# IOTA-GFT-Shield-a.net
KiCad netlist of a schematic drawn in EAGLE
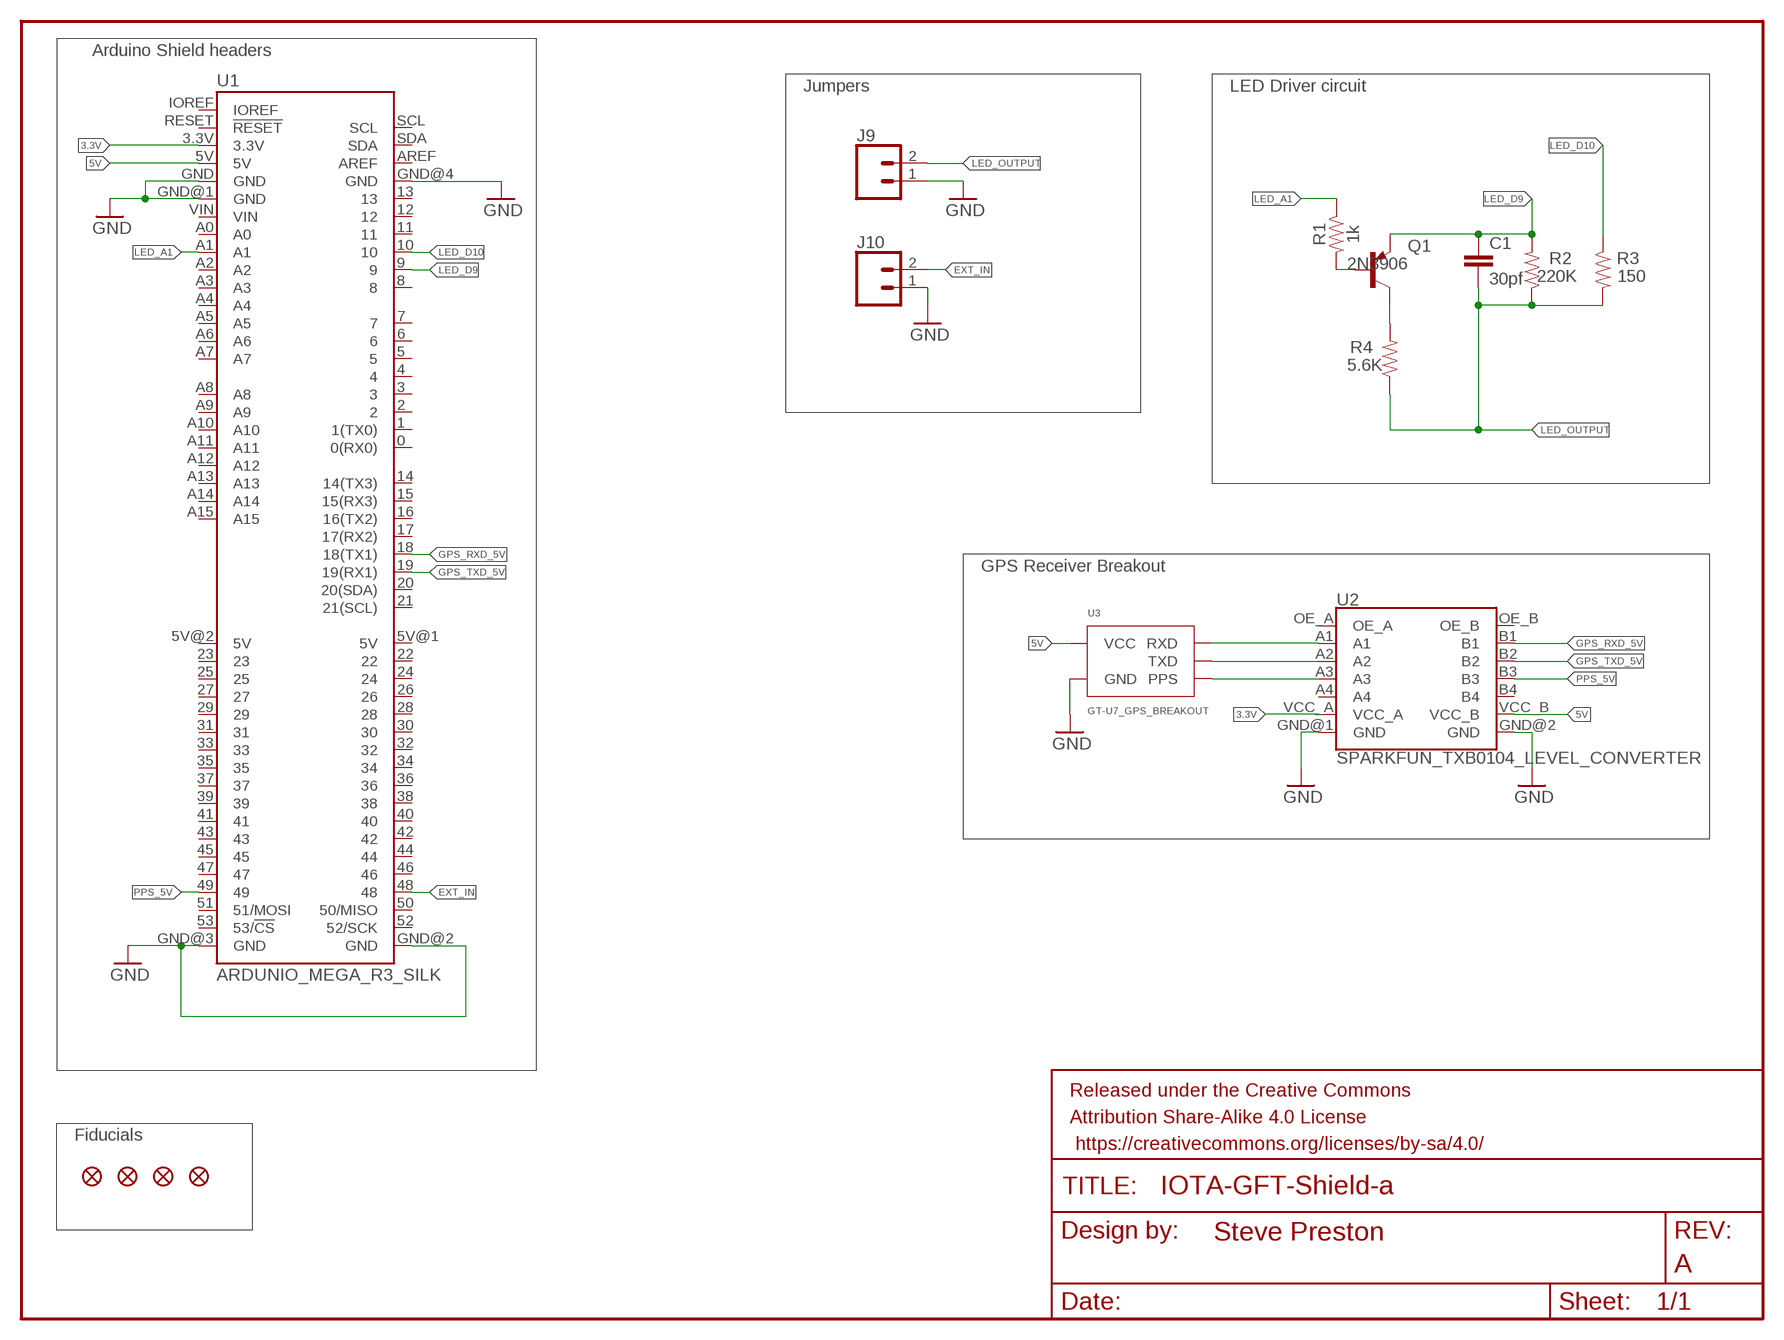
[diagram p0: schematic, sheet 1]

(export (version "E")
  (design (tool "Eeschema 10.0.6"))
  (components
    (comp (ref "C1")
      (value "30pf")
      (footprint "eagle-import:CAP-PTH-5MM")
      (libsource (lib "eagle-import") (part "CAP-PTH"))
    )
    (comp (ref "FD1")
      (value "FIDUCIALUFIDUCIAL")
      (footprint "eagle-import:FIDUCIAL-MICRO")
      (libsource (lib "eagle-import") (part "FIDUCIALUFIDUCIAL"))
    )
    (comp (ref "FD2")
      (value "FIDUCIALUFIDUCIAL")
      (footprint "eagle-import:FIDUCIAL-MICRO")
      (libsource (lib "eagle-import") (part "FIDUCIALUFIDUCIAL"))
    )
    (comp (ref "FD3")
      (value "FIDUCIALUFIDUCIAL")
      (footprint "eagle-import:FIDUCIAL-MICRO")
      (libsource (lib "eagle-import") (part "FIDUCIALUFIDUCIAL"))
    )
    (comp (ref "FD4")
      (value "FIDUCIALUFIDUCIAL")
      (footprint "eagle-import:FIDUCIAL-MICRO")
      (libsource (lib "eagle-import") (part "FIDUCIALUFIDUCIAL"))
    )
    (comp (ref "FRAME1")
      (value "FRAME-LETTER")
      (footprint "eagle-import:CREATIVE_COMMONS")
      (fields (field (name "DESIGNER") "Steve Preston") (field (name "REV") "A"))
      (libsource (lib "eagle-import") (part "FRAME-LETTER"))
    )
    (comp (ref "J9")
      (value "CONN_02")
      (footprint "eagle-import:1X02")
      (libsource (lib "eagle-import") (part "CONN_02"))
    )
    (comp (ref "J10")
      (value "CONN_02")
      (footprint "eagle-import:1X02")
      (libsource (lib "eagle-import") (part "CONN_02"))
    )
    (comp (ref "Q1")
      (value "2N3906")
      (footprint "eagle-import:TO92")
      (libsource (lib "eagle-import") (part "2N3906"))
    )
    (comp (ref "R1")
      (value "1k")
      (footprint "eagle-import:AXIAL-0.3")
      (libsource (lib "eagle-import") (part "1KOHM-HORIZ-1/4W-1%"))
    )
    (comp (ref "R2")
      (value "220K")
      (footprint "eagle-import:AXIAL-0.3")
      (libsource (lib "eagle-import") (part "1KOHM-HORIZ-1/4W-1%"))
    )
    (comp (ref "R3")
      (value "150")
      (footprint "eagle-import:AXIAL-0.3")
      (libsource (lib "eagle-import") (part "1KOHM-HORIZ-1/4W-1%"))
    )
    (comp (ref "R4")
      (value "5.6K")
      (footprint "eagle-import:AXIAL-0.3")
      (libsource (lib "eagle-import") (part "RESISTORAXIAL-0.3"))
    )
    (comp (ref "U1")
      (value "ARDUNIO_MEGA_R3_SILK")
      (footprint "eagle-import:ARDUINO_MEGA_SILK")
      (libsource (lib "eagle-import") (part "ARDUNIO_MEGA_R3_SILK"))
    )
    (comp (ref "U2")
      (value "SPARKFUN_TXB0104_LEVEL_CONVERTER")
      (footprint "eagle-import:TXB0104_LEVEL_CONVERTER")
      (libsource (lib "eagle-import") (part "SPARKFUN_TXB0104_LEVEL_CONVERTER"))
    )
    (comp (ref "U3")
      (value "GT-U7_GPS_BREAKOUT")
      (footprint "eagle-import:GT-UT")
      (libsource (lib "eagle-import") (part "GT-U7_GPS_BREAKOUT"))
    )
  )
  (nets
    (net (code "1") (name "3.3V") (class "Default")
      (node (ref "U1") (pin "3.3V") (pinfunction "3.3V_3.3V") (pintype "bidirectional"))
      (node (ref "U2") (pin "VCC_A") (pinfunction "VCC_A_VCC_A") (pintype "power_in"))
    )
    (net (code "2") (name "5V") (class "Default")
      (node (ref "U1") (pin "5V") (pinfunction "5V_5V") (pintype "bidirectional"))
      (node (ref "U2") (pin "VCC_B") (pinfunction "VCC_B_VCC_B") (pintype "power_in"))
      (node (ref "U3") (pin "VCC") (pinfunction "VCC_VCC") (pintype "power_in"))
    )
    (net (code "3") (name "EXT_IN") (class "Default")
      (node (ref "J10") (pin "2") (pinfunction "2_2") (pintype "passive"))
      (node (ref "U1") (pin "48") (pinfunction "48_48") (pintype "bidirectional"))
    )
    (net (code "4") (name "GND") (class "Default")
      (node (ref "J10") (pin "1") (pinfunction "1_1") (pintype "passive"))
      (node (ref "J9") (pin "1") (pinfunction "1_1") (pintype "passive"))
      (node (ref "U1") (pin "GND") (pinfunction "GND_GND") (pintype "bidirectional"))
      (node (ref "U1") (pin "GND@1") (pinfunction "GND_GND@1") (pintype "bidirectional"))
      (node (ref "U1") (pin "GND@2") (pinfunction "GND_GND@2") (pintype "bidirectional"))
      (node (ref "U1") (pin "GND@3") (pinfunction "GND_GND@3") (pintype "bidirectional"))
      (node (ref "U1") (pin "GND@4") (pinfunction "GND_GND@4") (pintype "bidirectional"))
      (node (ref "U2") (pin "GND@1") (pinfunction "GND_GND@1") (pintype "power_in"))
      (node (ref "U2") (pin "GND@2") (pinfunction "GND_GND@2") (pintype "power_in"))
      (node (ref "U3") (pin "GND") (pinfunction "GND_GND") (pintype "power_in"))
    )
    (net (code "5") (name "GPS_RXD_5V") (class "Default")
      (node (ref "U1") (pin "18") (pinfunction "18(TX1)_18") (pintype "bidirectional"))
      (node (ref "U2") (pin "B1") (pinfunction "B1_B1") (pintype "bidirectional"))
    )
    (net (code "6") (name "GPS_TXD_5V") (class "Default")
      (node (ref "U1") (pin "19") (pinfunction "19(RX1)_19") (pintype "bidirectional"))
      (node (ref "U2") (pin "B2") (pinfunction "B2_B2") (pintype "bidirectional"))
    )
    (net (code "7") (name "LED_A1") (class "Default")
      (node (ref "R1") (pin "P$1") (pinfunction "1_P$1") (pintype "passive"))
      (node (ref "U1") (pin "A1") (pinfunction "A1_A1") (pintype "bidirectional"))
    )
    (net (code "8") (name "LED_D9") (class "Default")
      (node (ref "C1") (pin "1") (pinfunction "1_1") (pintype "passive"))
      (node (ref "Q1") (pin "3") (pinfunction "E_3") (pintype "passive"))
      (node (ref "R2") (pin "P$2") (pinfunction "2_P$2") (pintype "passive"))
      (node (ref "U1") (pin "9") (pinfunction "9_9") (pintype "bidirectional"))
    )
    (net (code "9") (name "LED_D10") (class "Default")
      (node (ref "R3") (pin "P$1") (pinfunction "1_P$1") (pintype "passive"))
      (node (ref "U1") (pin "10") (pinfunction "10_10") (pintype "bidirectional"))
    )
    (net (code "10") (name "LED_OUTPUT") (class "Default")
      (node (ref "C1") (pin "2") (pinfunction "2_2") (pintype "passive"))
      (node (ref "J9") (pin "2") (pinfunction "2_2") (pintype "passive"))
      (node (ref "R2") (pin "P$1") (pinfunction "1_P$1") (pintype "passive"))
      (node (ref "R3") (pin "P$2") (pinfunction "2_P$2") (pintype "passive"))
      (node (ref "R4") (pin "P$1") (pinfunction "1_P$1") (pintype "passive"))
    )
    (net (code "11") (name "Net-(Q1-B)") (class "Default")
      (node (ref "Q1") (pin "2") (pinfunction "B_2") (pintype "passive"))
      (node (ref "R1") (pin "P$2") (pinfunction "2_P$2") (pintype "passive"))
    )
    (net (code "12") (name "Net-(Q1-C)") (class "Default")
      (node (ref "Q1") (pin "1") (pinfunction "C_1") (pintype "passive"))
      (node (ref "R4") (pin "P$2") (pinfunction "2_P$2") (pintype "passive"))
    )
    (net (code "13") (name "Net-(U2-PadA1)") (class "Default")
      (node (ref "U2") (pin "A1") (pinfunction "A1_A1") (pintype "bidirectional"))
      (node (ref "U3") (pin "RXD") (pinfunction "RXD_RXD") (pintype "bidirectional"))
    )
    (net (code "14") (name "Net-(U2-PadA2)") (class "Default")
      (node (ref "U2") (pin "A2") (pinfunction "A2_A2") (pintype "bidirectional"))
      (node (ref "U3") (pin "TXD") (pinfunction "TXD_TXD") (pintype "bidirectional"))
    )
    (net (code "15") (name "Net-(U2-PadA3)") (class "Default")
      (node (ref "U2") (pin "A3") (pinfunction "A3_A3") (pintype "bidirectional"))
      (node (ref "U3") (pin "PPS") (pinfunction "PPS_PPS") (pintype "bidirectional"))
    )
    (net (code "16") (name "PPS_5V") (class "Default")
      (node (ref "U1") (pin "49") (pinfunction "49_49") (pintype "bidirectional"))
      (node (ref "U2") (pin "B3") (pinfunction "B3_B3") (pintype "bidirectional"))
    )
    (net (code "17") (name "unconnected-(U1-0(RX0)-Pad0)") (class "Default")
      (node (ref "U1") (pin "0") (pinfunction "0(RX0)_0") (pintype "bidirectional"))
    )
    (net (code "18") (name "unconnected-(U1-1(TX0)-Pad1)") (class "Default")
      (node (ref "U1") (pin "1") (pinfunction "1(TX0)_1") (pintype "bidirectional"))
    )
    (net (code "19") (name "unconnected-(U1-5V-Pad5V@1)") (class "Default")
      (node (ref "U1") (pin "5V@1") (pinfunction "5V_5V@1") (pintype "bidirectional"))
    )
    (net (code "20") (name "unconnected-(U1-5V-Pad5V@2)") (class "Default")
      (node (ref "U1") (pin "5V@2") (pinfunction "5V_5V@2") (pintype "bidirectional"))
    )
    (net (code "21") (name "unconnected-(U1-14(TX3)-Pad14)") (class "Default")
      (node (ref "U1") (pin "14") (pinfunction "14(TX3)_14") (pintype "bidirectional"))
    )
    (net (code "22") (name "unconnected-(U1-15(RX3)-Pad15)") (class "Default")
      (node (ref "U1") (pin "15") (pinfunction "15(RX3)_15") (pintype "bidirectional"))
    )
    (net (code "23") (name "unconnected-(U1-16(TX2)-Pad16)") (class "Default")
      (node (ref "U1") (pin "16") (pinfunction "16(TX2)_16") (pintype "bidirectional"))
    )
    (net (code "24") (name "unconnected-(U1-17(RX2)-Pad17)") (class "Default")
      (node (ref "U1") (pin "17") (pinfunction "17(RX2)_17") (pintype "bidirectional"))
    )
    (net (code "25") (name "unconnected-(U1-20(SDA)-Pad20)") (class "Default")
      (node (ref "U1") (pin "20") (pinfunction "20(SDA)_20") (pintype "bidirectional"))
    )
    (net (code "26") (name "unconnected-(U1-21(SCL)-Pad21)") (class "Default")
      (node (ref "U1") (pin "21") (pinfunction "21(SCL)_21") (pintype "bidirectional"))
    )
    (net (code "27") (name "unconnected-(U1-50{slash}MISO-Pad50)") (class "Default")
      (node (ref "U1") (pin "50") (pinfunction "50/MISO_50") (pintype "bidirectional"))
    )
    (net (code "28") (name "unconnected-(U1-51{slash}MOSI-Pad51)") (class "Default")
      (node (ref "U1") (pin "51") (pinfunction "51/MOSI_51") (pintype "bidirectional"))
    )
    (net (code "29") (name "unconnected-(U1-52{slash}SCK-Pad52)") (class "Default")
      (node (ref "U1") (pin "52") (pinfunction "52/SCK_52") (pintype "bidirectional"))
    )
    (net (code "30") (name "unconnected-(U1-53{slash}~{CS}-Pad53)") (class "Default")
      (node (ref "U1") (pin "53") (pinfunction "53/~{CS}_53") (pintype "bidirectional"))
    )
    (net (code "31") (name "unconnected-(U1-Pad2)") (class "Default")
      (node (ref "U1") (pin "2") (pinfunction "2_2") (pintype "bidirectional"))
    )
    (net (code "32") (name "unconnected-(U1-Pad3)") (class "Default")
      (node (ref "U1") (pin "3") (pinfunction "3_3") (pintype "bidirectional"))
    )
    (net (code "33") (name "unconnected-(U1-Pad4)") (class "Default")
      (node (ref "U1") (pin "4") (pinfunction "4_4") (pintype "bidirectional"))
    )
    (net (code "34") (name "unconnected-(U1-Pad5)") (class "Default")
      (node (ref "U1") (pin "5") (pinfunction "5_5") (pintype "bidirectional"))
    )
    (net (code "35") (name "unconnected-(U1-Pad6)") (class "Default")
      (node (ref "U1") (pin "6") (pinfunction "6_6") (pintype "bidirectional"))
    )
    (net (code "36") (name "unconnected-(U1-Pad7)") (class "Default")
      (node (ref "U1") (pin "7") (pinfunction "7_7") (pintype "bidirectional"))
    )
    (net (code "37") (name "unconnected-(U1-Pad8)") (class "Default")
      (node (ref "U1") (pin "8") (pinfunction "8_8") (pintype "bidirectional"))
    )
    (net (code "38") (name "unconnected-(U1-Pad11)") (class "Default")
      (node (ref "U1") (pin "11") (pinfunction "11_11") (pintype "bidirectional"))
    )
    (net (code "39") (name "unconnected-(U1-Pad12)") (class "Default")
      (node (ref "U1") (pin "12") (pinfunction "12_12") (pintype "bidirectional"))
    )
    (net (code "40") (name "unconnected-(U1-Pad13)") (class "Default")
      (node (ref "U1") (pin "13") (pinfunction "13_13") (pintype "bidirectional"))
    )
    (net (code "41") (name "unconnected-(U1-Pad22)") (class "Default")
      (node (ref "U1") (pin "22") (pinfunction "22_22") (pintype "bidirectional"))
    )
    (net (code "42") (name "unconnected-(U1-Pad23)") (class "Default")
      (node (ref "U1") (pin "23") (pinfunction "23_23") (pintype "bidirectional"))
    )
    (net (code "43") (name "unconnected-(U1-Pad24)") (class "Default")
      (node (ref "U1") (pin "24") (pinfunction "24_24") (pintype "bidirectional"))
    )
    (net (code "44") (name "unconnected-(U1-Pad25)") (class "Default")
      (node (ref "U1") (pin "25") (pinfunction "25_25") (pintype "bidirectional"))
    )
    (net (code "45") (name "unconnected-(U1-Pad26)") (class "Default")
      (node (ref "U1") (pin "26") (pinfunction "26_26") (pintype "bidirectional"))
    )
    (net (code "46") (name "unconnected-(U1-Pad27)") (class "Default")
      (node (ref "U1") (pin "27") (pinfunction "27_27") (pintype "bidirectional"))
    )
    (net (code "47") (name "unconnected-(U1-Pad28)") (class "Default")
      (node (ref "U1") (pin "28") (pinfunction "28_28") (pintype "bidirectional"))
    )
    (net (code "48") (name "unconnected-(U1-Pad29)") (class "Default")
      (node (ref "U1") (pin "29") (pinfunction "29_29") (pintype "bidirectional"))
    )
    (net (code "49") (name "unconnected-(U1-Pad30)") (class "Default")
      (node (ref "U1") (pin "30") (pinfunction "30_30") (pintype "bidirectional"))
    )
    (net (code "50") (name "unconnected-(U1-Pad31)") (class "Default")
      (node (ref "U1") (pin "31") (pinfunction "31_31") (pintype "bidirectional"))
    )
    (net (code "51") (name "unconnected-(U1-Pad32)") (class "Default")
      (node (ref "U1") (pin "32") (pinfunction "32_32") (pintype "bidirectional"))
    )
    (net (code "52") (name "unconnected-(U1-Pad33)") (class "Default")
      (node (ref "U1") (pin "33") (pinfunction "33_33") (pintype "bidirectional"))
    )
    (net (code "53") (name "unconnected-(U1-Pad34)") (class "Default")
      (node (ref "U1") (pin "34") (pinfunction "34_34") (pintype "bidirectional"))
    )
    (net (code "54") (name "unconnected-(U1-Pad35)") (class "Default")
      (node (ref "U1") (pin "35") (pinfunction "35_35") (pintype "bidirectional"))
    )
    (net (code "55") (name "unconnected-(U1-Pad36)") (class "Default")
      (node (ref "U1") (pin "36") (pinfunction "36_36") (pintype "bidirectional"))
    )
    (net (code "56") (name "unconnected-(U1-Pad37)") (class "Default")
      (node (ref "U1") (pin "37") (pinfunction "37_37") (pintype "bidirectional"))
    )
    (net (code "57") (name "unconnected-(U1-Pad38)") (class "Default")
      (node (ref "U1") (pin "38") (pinfunction "38_38") (pintype "bidirectional"))
    )
    (net (code "58") (name "unconnected-(U1-Pad39)") (class "Default")
      (node (ref "U1") (pin "39") (pinfunction "39_39") (pintype "bidirectional"))
    )
    (net (code "59") (name "unconnected-(U1-Pad40)") (class "Default")
      (node (ref "U1") (pin "40") (pinfunction "40_40") (pintype "bidirectional"))
    )
    (net (code "60") (name "unconnected-(U1-Pad41)") (class "Default")
      (node (ref "U1") (pin "41") (pinfunction "41_41") (pintype "bidirectional"))
    )
    (net (code "61") (name "unconnected-(U1-Pad42)") (class "Default")
      (node (ref "U1") (pin "42") (pinfunction "42_42") (pintype "bidirectional"))
    )
    (net (code "62") (name "unconnected-(U1-Pad43)") (class "Default")
      (node (ref "U1") (pin "43") (pinfunction "43_43") (pintype "bidirectional"))
    )
    (net (code "63") (name "unconnected-(U1-Pad44)") (class "Default")
      (node (ref "U1") (pin "44") (pinfunction "44_44") (pintype "bidirectional"))
    )
    (net (code "64") (name "unconnected-(U1-Pad45)") (class "Default")
      (node (ref "U1") (pin "45") (pinfunction "45_45") (pintype "bidirectional"))
    )
    (net (code "65") (name "unconnected-(U1-Pad46)") (class "Default")
      (node (ref "U1") (pin "46") (pinfunction "46_46") (pintype "bidirectional"))
    )
    (net (code "66") (name "unconnected-(U1-Pad47)") (class "Default")
      (node (ref "U1") (pin "47") (pinfunction "47_47") (pintype "bidirectional"))
    )
    (net (code "67") (name "unconnected-(U1-PadA0)") (class "Default")
      (node (ref "U1") (pin "A0") (pinfunction "A0_A0") (pintype "bidirectional"))
    )
    (net (code "68") (name "unconnected-(U1-PadA2)") (class "Default")
      (node (ref "U1") (pin "A2") (pinfunction "A2_A2") (pintype "bidirectional"))
    )
    (net (code "69") (name "unconnected-(U1-PadA3)") (class "Default")
      (node (ref "U1") (pin "A3") (pinfunction "A3_A3") (pintype "bidirectional"))
    )
    (net (code "70") (name "unconnected-(U1-PadA4)") (class "Default")
      (node (ref "U1") (pin "A4") (pinfunction "A4_A4") (pintype "bidirectional"))
    )
    (net (code "71") (name "unconnected-(U1-PadA5)") (class "Default")
      (node (ref "U1") (pin "A5") (pinfunction "A5_A5") (pintype "bidirectional"))
    )
    (net (code "72") (name "unconnected-(U1-PadA6)") (class "Default")
      (node (ref "U1") (pin "A6") (pinfunction "A6_A6") (pintype "bidirectional"))
    )
    (net (code "73") (name "unconnected-(U1-PadA7)") (class "Default")
      (node (ref "U1") (pin "A7") (pinfunction "A7_A7") (pintype "bidirectional"))
    )
    (net (code "74") (name "unconnected-(U1-PadA8)") (class "Default")
      (node (ref "U1") (pin "A8") (pinfunction "A8_A8") (pintype "bidirectional"))
    )
    (net (code "75") (name "unconnected-(U1-PadA9)") (class "Default")
      (node (ref "U1") (pin "A9") (pinfunction "A9_A9") (pintype "bidirectional"))
    )
    (net (code "76") (name "unconnected-(U1-PadA10)") (class "Default")
      (node (ref "U1") (pin "A10") (pinfunction "A10_A10") (pintype "bidirectional"))
    )
    (net (code "77") (name "unconnected-(U1-PadA11)") (class "Default")
      (node (ref "U1") (pin "A11") (pinfunction "A11_A11") (pintype "bidirectional"))
    )
    (net (code "78") (name "unconnected-(U1-PadA12)") (class "Default")
      (node (ref "U1") (pin "A12") (pinfunction "A12_A12") (pintype "bidirectional"))
    )
    (net (code "79") (name "unconnected-(U1-PadA13)") (class "Default")
      (node (ref "U1") (pin "A13") (pinfunction "A13_A13") (pintype "bidirectional"))
    )
    (net (code "80") (name "unconnected-(U1-PadA14)") (class "Default")
      (node (ref "U1") (pin "A14") (pinfunction "A14_A14") (pintype "bidirectional"))
    )
    (net (code "81") (name "unconnected-(U1-PadA15)") (class "Default")
      (node (ref "U1") (pin "A15") (pinfunction "A15_A15") (pintype "bidirectional"))
    )
    (net (code "82") (name "unconnected-(U1-PadAREF)") (class "Default")
      (node (ref "U1") (pin "AREF") (pinfunction "AREF_AREF") (pintype "bidirectional"))
    )
    (net (code "83") (name "unconnected-(U1-PadIOREF)") (class "Default")
      (node (ref "U1") (pin "IOREF") (pinfunction "IOREF_IOREF") (pintype "bidirectional"))
    )
    (net (code "84") (name "unconnected-(U1-PadSCL)") (class "Default")
      (node (ref "U1") (pin "SCL") (pinfunction "SCL_SCL") (pintype "bidirectional"))
    )
    (net (code "85") (name "unconnected-(U1-PadSDA)") (class "Default")
      (node (ref "U1") (pin "SDA") (pinfunction "SDA_SDA") (pintype "bidirectional"))
    )
    (net (code "86") (name "unconnected-(U1-PadVIN)") (class "Default")
      (node (ref "U1") (pin "VIN") (pinfunction "VIN_VIN") (pintype "bidirectional"))
    )
    (net (code "87") (name "unconnected-(U1-~{RESET}-PadRESET)") (class "Default")
      (node (ref "U1") (pin "RESET") (pinfunction "~{RESET}_RESET") (pintype "bidirectional"))
    )
    (net (code "88") (name "unconnected-(U2-PadA4)") (class "Default")
      (node (ref "U2") (pin "A4") (pinfunction "A4_A4") (pintype "bidirectional"))
    )
    (net (code "89") (name "unconnected-(U2-PadB4)") (class "Default")
      (node (ref "U2") (pin "B4") (pinfunction "B4_B4") (pintype "bidirectional"))
    )
    (net (code "90") (name "unconnected-(U2-PadOE_A)") (class "Default")
      (node (ref "U2") (pin "OE_A") (pinfunction "OE_A_OE_A") (pintype "bidirectional"))
    )
    (net (code "91") (name "unconnected-(U2-PadOE_B)") (class "Default")
      (node (ref "U2") (pin "OE_B") (pinfunction "OE_B_OE_B") (pintype "bidirectional"))
    )
  )
)
